# ArduWatch.net
KiCad netlist of a schematic drawn in EAGLE
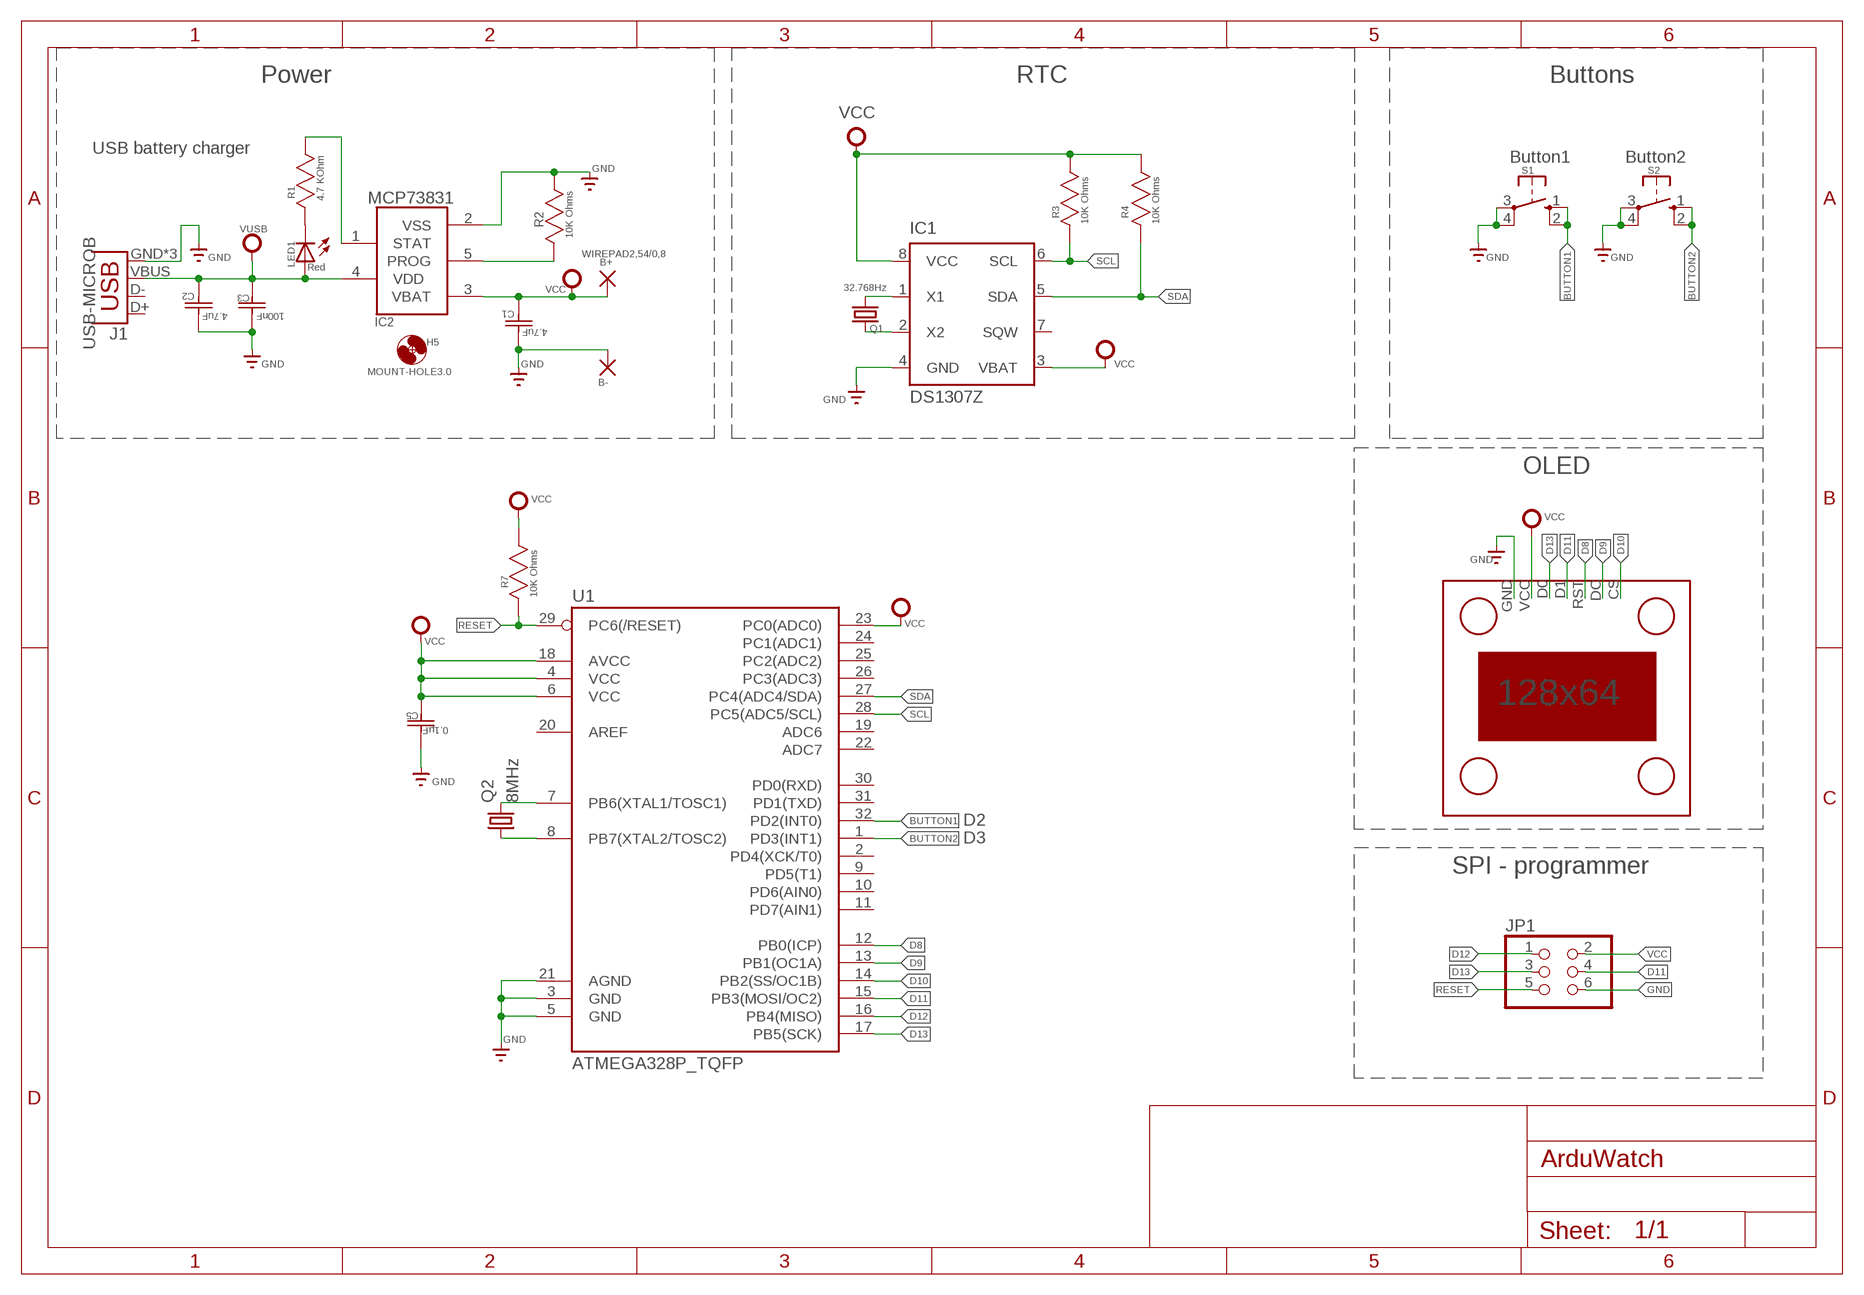
[diagram p0: schematic, sheet 1]

(export (version "E")
  (design (tool "Eeschema 10.0.6"))
  (components
    (comp (ref "1,3\"OLED1")
      (value "OLED")
      (footprint "eagle-import:1,3_OLED")
      (libsource (lib "eagle-import") (part "OLED"))
    )
    (comp (ref "B+")
      (value "WIREPAD2,54/0,8")
      (footprint "eagle-import:2,54_0,8")
      (libsource (lib "eagle-import") (part "WIREPAD2,54/0,8"))
    )
    (comp (ref "B-")
      (value "WIREPAD2,54/0,8")
      (footprint "eagle-import:2,54_0,8")
      (libsource (lib "eagle-import") (part "WIREPAD2,54/0,8"))
    )
    (comp (ref "C1")
      (value "4.7uF")
      (footprint "eagle-import:CAPC3216X180N")
      (fields (field (name "MPN") "C1206C475K3RACTU") (field (name "TOLERANCE") "±10%"))
      (libsource (lib "eagle-import") (part "C1206C475K3RACTU"))
    )
    (comp (ref "C2")
      (value "4.7uF")
      (footprint "eagle-import:CAPC3216X180N")
      (fields (field (name "MPN") "C1206C475K3RACTU") (field (name "TOLERANCE") "±10%"))
      (libsource (lib "eagle-import") (part "C1206C475K3RACTU"))
    )
    (comp (ref "C3")
      (value "100nF")
      (footprint "eagle-import:CAPC3216X88N")
      (fields (field (name "MPN") "C1206C104K1RACTU") (field (name "TOLERANCE") "±10%"))
      (libsource (lib "eagle-import") (part "C1206C104K1RACTU"))
    )
    (comp (ref "C5")
      (value "0.1µF")
      (footprint "eagle-import:CAPC3216X94N")
      (fields (field (name "MPN") "1206YC104KAT2A") (field (name "TOLERANCE") "±10%"))
      (libsource (lib "eagle-import") (part "1206YC104KAT2A"))
    )
    (comp (ref "H5")
      (value "MOUNT-HOLE3.0")
      (footprint "eagle-import:3,0")
      (libsource (lib "eagle-import") (part "MOUNT-HOLE3.0"))
    )
    (comp (ref "IC1")
      (value "DS1307Z")
      (footprint "eagle-import:SOIC8")
      (libsource (lib "eagle-import") (part "DS1307Z"))
    )
    (comp (ref "IC2")
      (value "MCP73831")
      (footprint "eagle-import:SOT23-5L")
      (libsource (lib "eagle-import") (part "MCP73831"))
    )
    (comp (ref "J1")
      (value "USB-MICROB")
      (footprint "eagle-import:USB-MICROB")
      (libsource (lib "eagle-import") (part "USB-MICROB"))
    )
    (comp (ref "JP1")
      (value "PINHD-2X3")
      (footprint "eagle-import:2X03")
      (libsource (lib "eagle-import") (part "PINHD-2X3"))
    )
    (comp (ref "LED1")
      (value "Red")
      (footprint "eagle-import:CHIPLED_1206")
      (libsource (lib "eagle-import") (part "LEDCHIPLED_1206"))
    )
    (comp (ref "Q1")
      (value "32.768Hz")
      (footprint "eagle-import:TC26H")
      (libsource (lib "eagle-import") (part "CRYSTALTC26H"))
    )
    (comp (ref "Q2")
      (value "8MHz")
      (footprint "eagle-import:HC49_S")
      (libsource (lib "eagle-import") (part "CRYSTALHC49S"))
    )
    (comp (ref "R1")
      (value "4.7 KOhm")
      (footprint "eagle-import:RESC3216X71N")
      (fields (field (name "MPN") "ERJ-8ENF4701V") (field (name "TOLERANCE") "±1 %"))
      (libsource (lib "eagle-import") (part "ERJ-8ENF4701V"))
    )
    (comp (ref "R2")
      (value "10K Ohms")
      (footprint "eagle-import:RESC3216X71N")
      (fields (field (name "MPN") "MC0.125W12061%10K") (field (name "TOLERANCE") "±1%"))
      (libsource (lib "eagle-import") (part "MC0.125W12061%10K"))
    )
    (comp (ref "R3")
      (value "10K Ohms")
      (footprint "eagle-import:RESC3216X71N")
      (fields (field (name "MPN") "MC0.125W12061%10K") (field (name "TOLERANCE") "±1%"))
      (libsource (lib "eagle-import") (part "MC0.125W12061%10K"))
    )
    (comp (ref "R4")
      (value "10K Ohms")
      (footprint "eagle-import:RESC3216X71N")
      (fields (field (name "MPN") "MC0.125W12061%10K") (field (name "TOLERANCE") "±1%"))
      (libsource (lib "eagle-import") (part "MC0.125W12061%10K"))
    )
    (comp (ref "R7")
      (value "10K Ohms")
      (footprint "eagle-import:RESC3216X71N")
      (fields (field (name "MPN") "MC0.125W12061%10K") (field (name "TOLERANCE") "±1%"))
      (libsource (lib "eagle-import") (part "MC0.125W12061%10K"))
    )
    (comp (ref "S1")
      (value "Button1")
      (footprint "eagle-import:B3F-10XX")
      (fields (field (name "MPN") "B3F-1000"))
      (libsource (lib "eagle-import") (part "10-XX"))
    )
    (comp (ref "S2")
      (value "Button2")
      (footprint "eagle-import:B3F-10XX")
      (fields (field (name "MPN") "B3F-1000"))
      (libsource (lib "eagle-import") (part "10-XX"))
    )
    (comp (ref "U1")
      (value "ATMEGA328P_TQFP")
      (footprint "eagle-import:TQFP32-08")
      (libsource (lib "eagle-import") (part "ATMEGA328P_TQFP"))
    )
  )
  (nets
    (net (code "1") (name "BUTTON1") (class "Default")
      (node (ref "S1") (pin "1") (pinfunction "S_1") (pintype "passive"))
      (node (ref "S1") (pin "2") (pinfunction "S1_2") (pintype "passive"))
      (node (ref "U1") (pin "32") (pinfunction "PD2(INT0)_32") (pintype "bidirectional"))
    )
    (net (code "2") (name "BUTTON2") (class "Default")
      (node (ref "S2") (pin "1") (pinfunction "S_1") (pintype "passive"))
      (node (ref "S2") (pin "2") (pinfunction "S1_2") (pintype "passive"))
      (node (ref "U1") (pin "1") (pinfunction "PD3(INT1)_1") (pintype "bidirectional"))
    )
    (net (code "3") (name "D8") (class "Default")
      (node (ref "1,3\"OLED1") (pin "RST") (pinfunction "RST_RST") (pintype "bidirectional"))
      (node (ref "U1") (pin "12") (pinfunction "PB0(ICP)_12") (pintype "bidirectional"))
    )
    (net (code "4") (name "D9") (class "Default")
      (node (ref "1,3\"OLED1") (pin "DC") (pinfunction "DC_DC") (pintype "bidirectional"))
      (node (ref "U1") (pin "13") (pinfunction "PB1(OC1A)_13") (pintype "bidirectional"))
    )
    (net (code "5") (name "D10") (class "Default")
      (node (ref "1,3\"OLED1") (pin "CS") (pinfunction "CS_CS") (pintype "bidirectional"))
      (node (ref "U1") (pin "14") (pinfunction "PB2(SS/OC1B)_14") (pintype "bidirectional"))
    )
    (net (code "6") (name "D11") (class "Default")
      (node (ref "1,3\"OLED1") (pin "D1") (pinfunction "D1_D1") (pintype "bidirectional"))
      (node (ref "JP1") (pin "4") (pinfunction "4_4") (pintype "passive"))
      (node (ref "U1") (pin "15") (pinfunction "PB3(MOSI/OC2)_15") (pintype "bidirectional"))
    )
    (net (code "7") (name "D12") (class "Default")
      (node (ref "JP1") (pin "1") (pinfunction "1_1") (pintype "passive"))
      (node (ref "U1") (pin "16") (pinfunction "PB4(MISO)_16") (pintype "bidirectional"))
    )
    (net (code "8") (name "D13") (class "Default")
      (node (ref "1,3\"OLED1") (pin "D0") (pinfunction "D0_D0") (pintype "bidirectional"))
      (node (ref "JP1") (pin "3") (pinfunction "3_3") (pintype "passive"))
      (node (ref "U1") (pin "17") (pinfunction "PB5(SCK)_17") (pintype "bidirectional"))
    )
    (net (code "9") (name "GND") (class "Default")
      (node (ref "1,3\"OLED1") (pin "GND") (pinfunction "GND_GND") (pintype "power_in"))
      (node (ref "B-") (pin "1") (pinfunction "P_1") (pintype "passive"))
      (node (ref "C1") (pin "1") (pinfunction "C1_1") (pintype "passive"))
      (node (ref "C2") (pin "1") (pinfunction "C1_1") (pintype "passive"))
      (node (ref "C3") (pin "1") (pinfunction "C1_1") (pintype "passive"))
      (node (ref "C5") (pin "1") (pinfunction "C1_1") (pintype "passive"))
      (node (ref "IC1") (pin "4") (pinfunction "GND_4") (pintype "power_in"))
      (node (ref "IC2") (pin "2") (pinfunction "VSS_2") (pintype "bidirectional"))
      (node (ref "J1") (pin "GND") (pinfunction "GND_GND") (pintype "bidirectional"))
      (node (ref "J1") (pin "MT1") (pinfunction "GND_MT1") (pintype "bidirectional"))
      (node (ref "J1") (pin "MT2") (pinfunction "GND_MT2") (pintype "bidirectional"))
      (node (ref "JP1") (pin "6") (pinfunction "6_6") (pintype "passive"))
      (node (ref "R2") (pin "1") (pinfunction "R1_1") (pintype "passive"))
      (node (ref "S1") (pin "3") (pinfunction "P_3") (pintype "passive"))
      (node (ref "S1") (pin "4") (pinfunction "P1_4") (pintype "passive"))
      (node (ref "S2") (pin "3") (pinfunction "P_3") (pintype "passive"))
      (node (ref "S2") (pin "4") (pinfunction "P1_4") (pintype "passive"))
      (node (ref "U1") (pin "21") (pinfunction "AGND_21") (pintype "bidirectional"))
      (node (ref "U1") (pin "3") (pinfunction "GND_3") (pintype "bidirectional"))
      (node (ref "U1") (pin "5") (pinfunction "GND_5") (pintype "bidirectional"))
    )
    (net (code "10") (name "Net-(IC1-X1)") (class "Default")
      (node (ref "IC1") (pin "1") (pinfunction "X1_1") (pintype "input"))
      (node (ref "Q1") (pin "2") (pinfunction "2_2") (pintype "passive"))
    )
    (net (code "11") (name "Net-(IC1-X2)") (class "Default")
      (node (ref "IC1") (pin "2") (pinfunction "X2_2") (pintype "output"))
      (node (ref "Q1") (pin "1") (pinfunction "1_1") (pintype "passive"))
    )
    (net (code "12") (name "Net-(IC2-PROG)") (class "Default")
      (node (ref "IC2") (pin "5") (pinfunction "PROG_5") (pintype "bidirectional"))
      (node (ref "R2") (pin "2") (pinfunction "R2_2") (pintype "passive"))
    )
    (net (code "13") (name "Net-(IC2-STAT)") (class "Default")
      (node (ref "IC2") (pin "1") (pinfunction "STAT_1") (pintype "bidirectional"))
      (node (ref "R1") (pin "1") (pinfunction "R1_1") (pintype "passive"))
    )
    (net (code "14") (name "Net-(R1-R2)") (class "Default")
      (node (ref "LED1") (pin "C") (pinfunction "C_C") (pintype "passive"))
      (node (ref "R1") (pin "2") (pinfunction "R2_2") (pintype "passive"))
    )
    (net (code "15") (name "Net-(U1-PB6(XTAL1{slash}TOSC1))") (class "Default")
      (node (ref "Q2") (pin "2") (pinfunction "2_2") (pintype "passive"))
      (node (ref "U1") (pin "7") (pinfunction "PB6(XTAL1/TOSC1)_7") (pintype "bidirectional"))
    )
    (net (code "16") (name "Net-(U1-PB7(XTAL2{slash}TOSC2))") (class "Default")
      (node (ref "Q2") (pin "1") (pinfunction "1_1") (pintype "passive"))
      (node (ref "U1") (pin "8") (pinfunction "PB7(XTAL2/TOSC2)_8") (pintype "bidirectional"))
    )
    (net (code "17") (name "RESET") (class "Default")
      (node (ref "JP1") (pin "5") (pinfunction "5_5") (pintype "passive"))
      (node (ref "R7") (pin "2") (pinfunction "R2_2") (pintype "passive"))
      (node (ref "U1") (pin "29") (pinfunction "PC6(/RESET)_29") (pintype "bidirectional"))
    )
    (net (code "18") (name "SCL") (class "Default")
      (node (ref "IC1") (pin "6") (pinfunction "SCL_6") (pintype "input"))
      (node (ref "R3") (pin "2") (pinfunction "R2_2") (pintype "passive"))
      (node (ref "U1") (pin "28") (pinfunction "PC5(ADC5/SCL)_28") (pintype "bidirectional"))
    )
    (net (code "19") (name "SDA") (class "Default")
      (node (ref "IC1") (pin "5") (pinfunction "SDA_5") (pintype "bidirectional"))
      (node (ref "R4") (pin "2") (pinfunction "R2_2") (pintype "passive"))
      (node (ref "U1") (pin "27") (pinfunction "PC4(ADC4/SDA)_27") (pintype "bidirectional"))
    )
    (net (code "20") (name "VCC") (class "Default")
      (node (ref "1,3\"OLED1") (pin "VCC") (pinfunction "VCC_VCC") (pintype "power_in"))
      (node (ref "B+") (pin "1") (pinfunction "P_1") (pintype "passive"))
      (node (ref "C1") (pin "2") (pinfunction "C2_2") (pintype "passive"))
      (node (ref "C5") (pin "2") (pinfunction "C2_2") (pintype "passive"))
      (node (ref "IC1") (pin "3") (pinfunction "VBAT_3") (pintype "passive"))
      (node (ref "IC1") (pin "8") (pinfunction "VCC_8") (pintype "power_in"))
      (node (ref "IC2") (pin "3") (pinfunction "VBAT_3") (pintype "bidirectional"))
      (node (ref "JP1") (pin "2") (pinfunction "2_2") (pintype "passive"))
      (node (ref "R3") (pin "1") (pinfunction "R1_1") (pintype "passive"))
      (node (ref "R4") (pin "1") (pinfunction "R1_1") (pintype "passive"))
      (node (ref "R7") (pin "1") (pinfunction "R1_1") (pintype "passive"))
      (node (ref "U1") (pin "18") (pinfunction "AVCC_18") (pintype "bidirectional"))
      (node (ref "U1") (pin "23") (pinfunction "PC0(ADC0)_23") (pintype "bidirectional"))
      (node (ref "U1") (pin "4") (pinfunction "VCC_4") (pintype "bidirectional"))
      (node (ref "U1") (pin "6") (pinfunction "VCC_6") (pintype "bidirectional"))
    )
    (net (code "21") (name "VUSB") (class "Default")
      (node (ref "C2") (pin "2") (pinfunction "C2_2") (pintype "passive"))
      (node (ref "C3") (pin "2") (pinfunction "C2_2") (pintype "passive"))
      (node (ref "IC2") (pin "4") (pinfunction "VDD_4") (pintype "bidirectional"))
      (node (ref "J1") (pin "VBUS") (pinfunction "VBUS_VBUS") (pintype "bidirectional"))
      (node (ref "LED1") (pin "A") (pinfunction "A_A") (pintype "passive"))
    )
    (net (code "22") (name "unconnected-(IC1-SQW-Pad7)") (class "Default")
      (node (ref "IC1") (pin "7") (pinfunction "SQW_7") (pintype "open_collector"))
    )
    (net (code "23") (name "unconnected-(J1-PadD+)") (class "Default")
      (node (ref "J1") (pin "D+") (pinfunction "D+_D+") (pintype "bidirectional"))
    )
    (net (code "24") (name "unconnected-(J1-PadD-)") (class "Default")
      (node (ref "J1") (pin "D-") (pinfunction "D-_D-") (pintype "bidirectional"))
    )
    (net (code "25") (name "unconnected-(U1-ADC6-Pad19)") (class "Default")
      (node (ref "U1") (pin "19") (pinfunction "ADC6_19") (pintype "bidirectional"))
    )
    (net (code "26") (name "unconnected-(U1-ADC7-Pad22)") (class "Default")
      (node (ref "U1") (pin "22") (pinfunction "ADC7_22") (pintype "bidirectional"))
    )
    (net (code "27") (name "unconnected-(U1-AREF-Pad20)") (class "Default")
      (node (ref "U1") (pin "20") (pinfunction "AREF_20") (pintype "bidirectional"))
    )
    (net (code "28") (name "unconnected-(U1-PC1(ADC1)-Pad24)") (class "Default")
      (node (ref "U1") (pin "24") (pinfunction "PC1(ADC1)_24") (pintype "bidirectional"))
    )
    (net (code "29") (name "unconnected-(U1-PC2(ADC2)-Pad25)") (class "Default")
      (node (ref "U1") (pin "25") (pinfunction "PC2(ADC2)_25") (pintype "bidirectional"))
    )
    (net (code "30") (name "unconnected-(U1-PC3(ADC3)-Pad26)") (class "Default")
      (node (ref "U1") (pin "26") (pinfunction "PC3(ADC3)_26") (pintype "bidirectional"))
    )
    (net (code "31") (name "unconnected-(U1-PD0(RXD)-Pad30)") (class "Default")
      (node (ref "U1") (pin "30") (pinfunction "PD0(RXD)_30") (pintype "bidirectional"))
    )
    (net (code "32") (name "unconnected-(U1-PD1(TXD)-Pad31)") (class "Default")
      (node (ref "U1") (pin "31") (pinfunction "PD1(TXD)_31") (pintype "bidirectional"))
    )
    (net (code "33") (name "unconnected-(U1-PD4(XCK{slash}T0)-Pad2)") (class "Default")
      (node (ref "U1") (pin "2") (pinfunction "PD4(XCK/T0)_2") (pintype "bidirectional"))
    )
    (net (code "34") (name "unconnected-(U1-PD5(T1)-Pad9)") (class "Default")
      (node (ref "U1") (pin "9") (pinfunction "PD5(T1)_9") (pintype "bidirectional"))
    )
    (net (code "35") (name "unconnected-(U1-PD6(AIN0)-Pad10)") (class "Default")
      (node (ref "U1") (pin "10") (pinfunction "PD6(AIN0)_10") (pintype "bidirectional"))
    )
    (net (code "36") (name "unconnected-(U1-PD7(AIN1)-Pad11)") (class "Default")
      (node (ref "U1") (pin "11") (pinfunction "PD7(AIN1)_11") (pintype "bidirectional"))
    )
  )
)
